# Connectors.net
KiCad netlist of a schematic drawn in Altium Designer
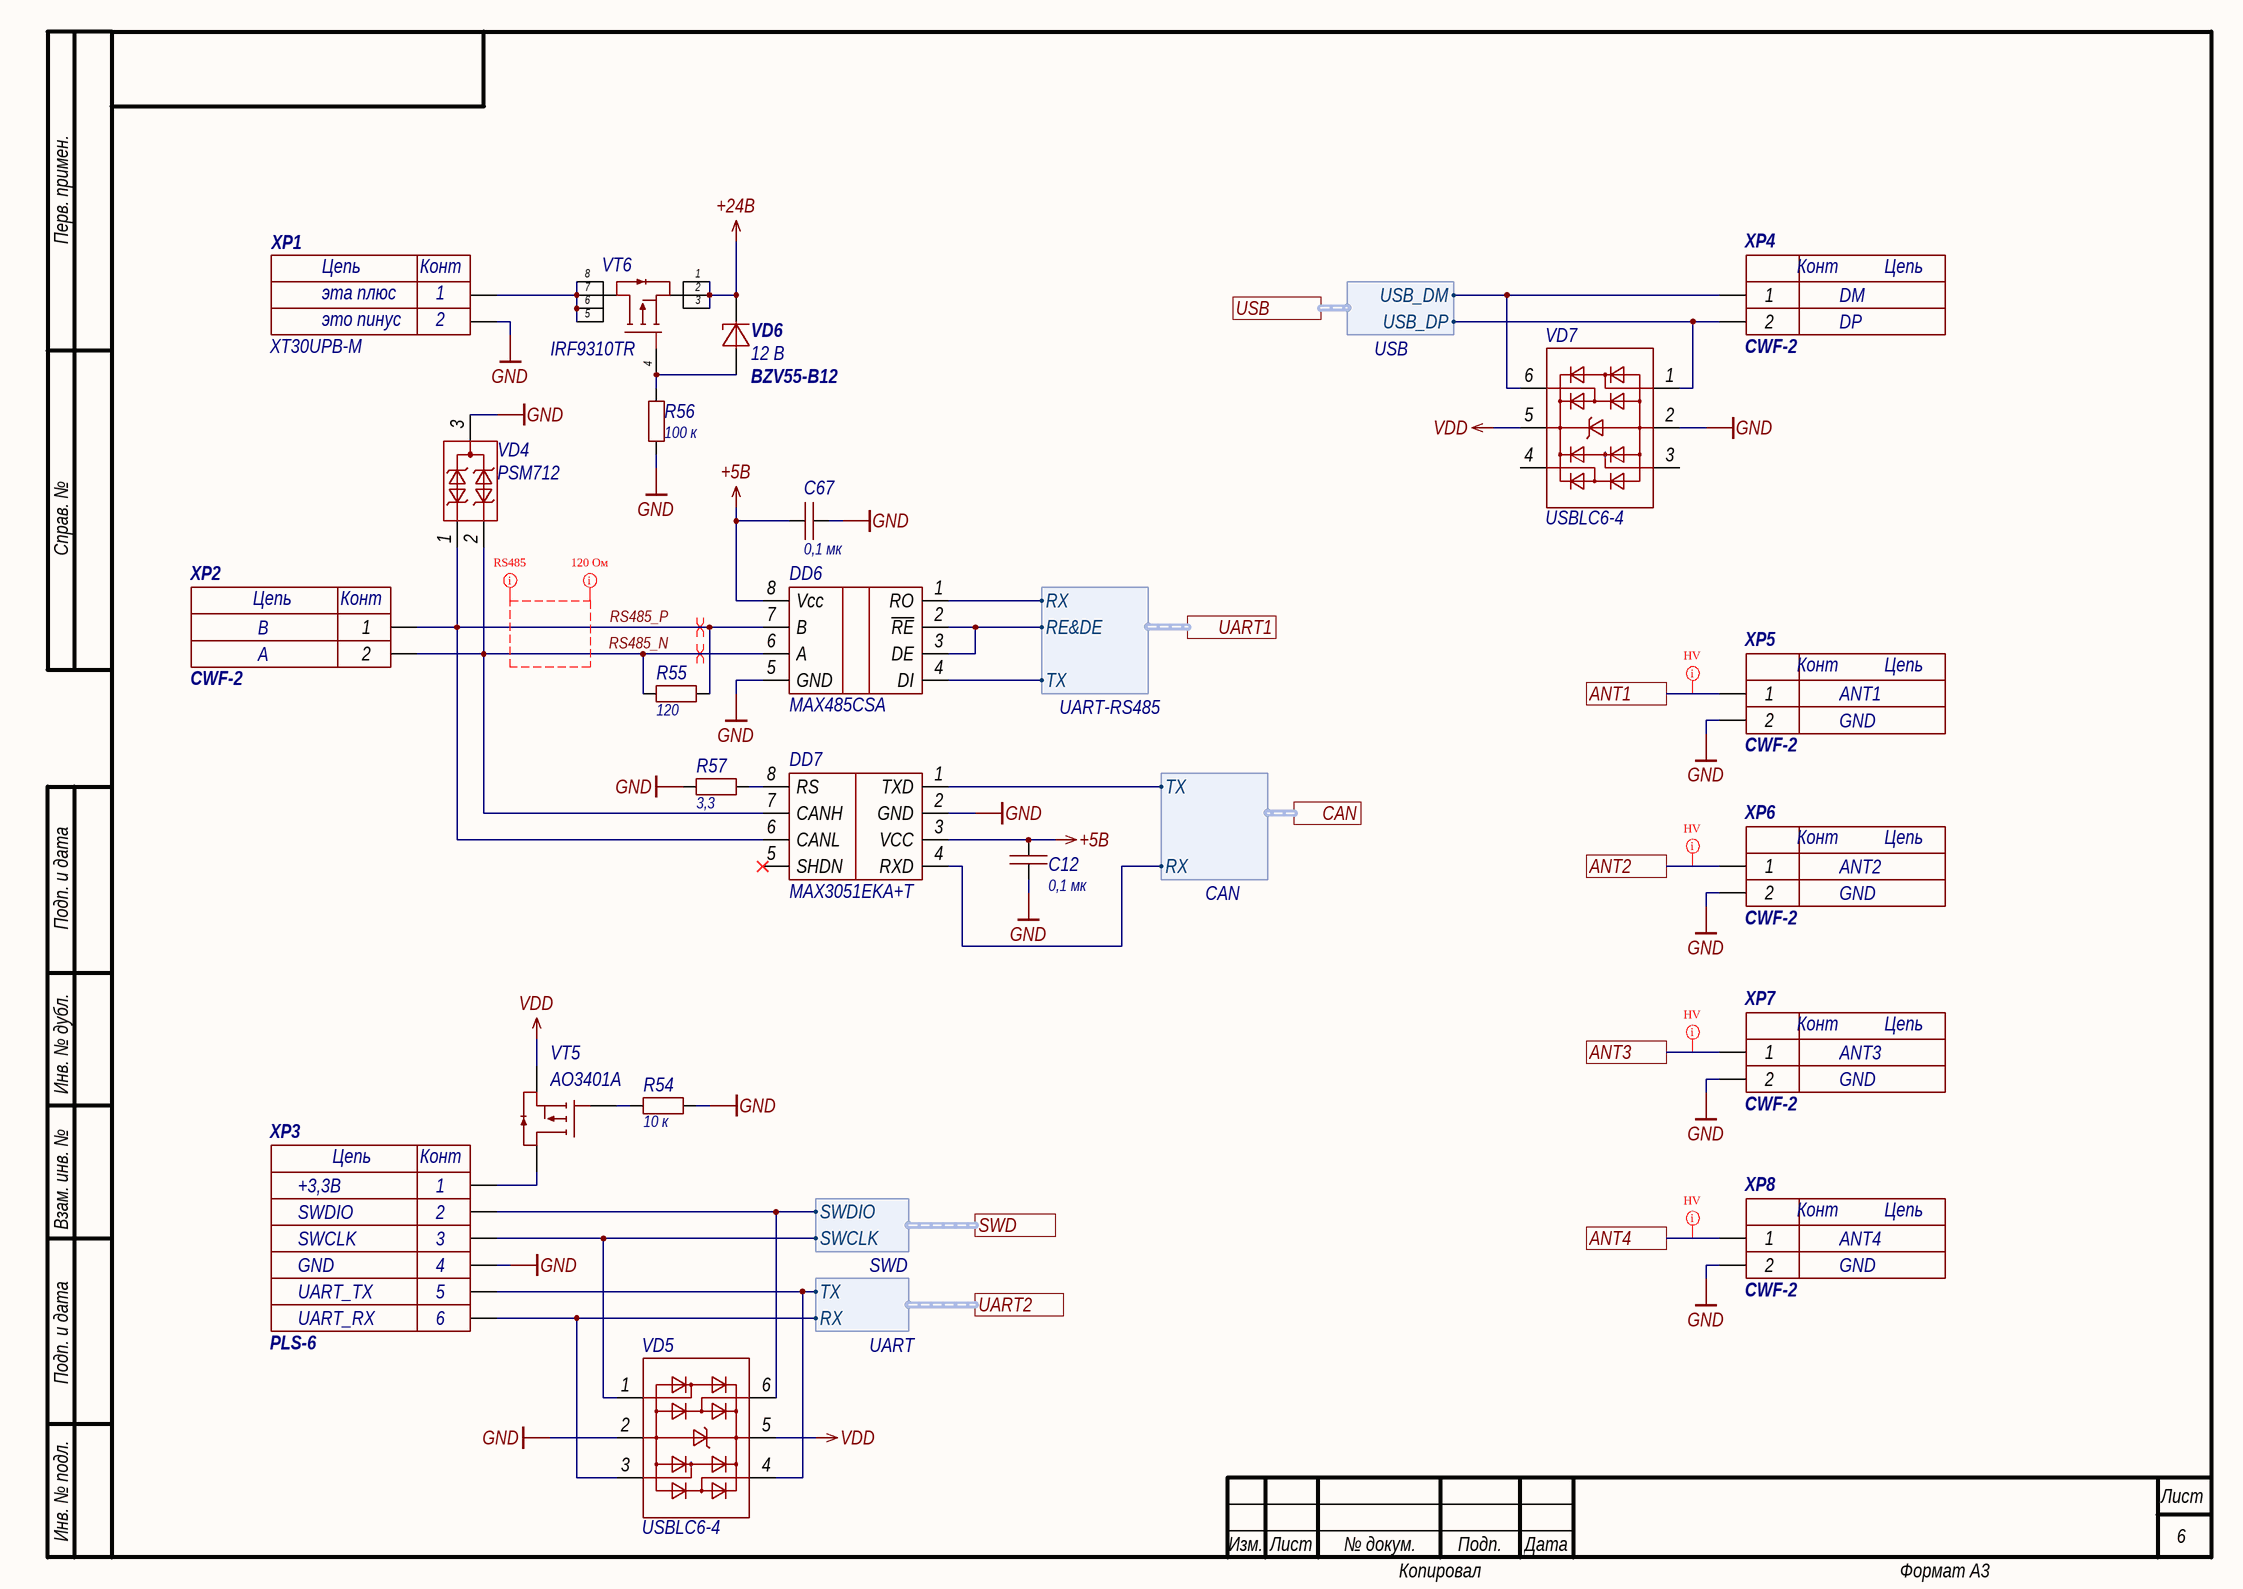
[diagram p0: Connectors.SchDoc]

(export (version "E")
  (design (tool "Eeschema 10.0.6"))
  (components
    (comp (ref "C12")
      (value "0,1 мк")
      (footprint "0603C")
      (description "Конденсатор 0603C ёмкостью 0,1 мк 10%, 50 В, X7R")
      (fields (field (name "PART NUMBER") "Capacitor_0,1u_10_50V_X7R_0603C") (field (name "TOLERANCE") "10%"))
      (libsource (lib "Hydrolib") (part "Capacitor"))
    )
    (comp (ref "C67")
      (value "0,1 мк")
      (footprint "0603C")
      (description "Конденсатор 0603C ёмкостью 0,1 мк 10%, 50 В, X7R")
      (fields (field (name "PART NUMBER") "Capacitor_0,1u_10_50V_X7R_0603C") (field (name "TOLERANCE") "10%"))
      (libsource (lib "Hydrolib") (part "Capacitor"))
    )
    (comp (ref "DD6")
      (value "MAX485CSA")
      (footprint "SOIC-8")
      (description "RS-485 приёмопередатчик")
      (libsource (lib "Hydrolib") (part "MAX485CSA"))
    )
    (comp (ref "DD7")
      (value "MAX3051EKA+T")
      (footprint "SOT23-8")
      (description "CAN трансивер 1Mbps +3.3В")
      (fields (field (name "АВТОР") "glebmih"))
      (libsource (lib "Hydrolib") (part "MAX3051EKA+T"))
    )
    (comp (ref "R54")
      (value "10 к")
      (footprint "0603R")
      (description "Резистор номиналом 10 кОм 1%")
      (fields (field (name "PART NUMBER") "Resistor_10k_1_0603") (field (name "TOLERANCE") "1%"))
      (libsource (lib "") (part "Resistor_1"))
    )
    (comp (ref "R55")
      (value "120")
      (footprint "1206R")
      (description "Резистор номиналом 120 Ом 1%")
      (fields
        (field (name "PART NUMBER") "Resistor_120_1_1206")
        (field (name "TOLERANCE") "1%")
        (field (name "АВТОР") "glebmih")
      )
      (libsource (lib "Hydrolib") (part "Resistor"))
    )
    (comp (ref "R56")
      (value "100 к")
      (footprint "0603R")
      (description "Резистор номиналом 100 кОм 1%")
      (fields (field (name "PART NUMBER") "Resistor_100k_1_0603") (field (name "TOLERANCE") "1%"))
      (libsource (lib "") (part "Resistor_2"))
    )
    (comp (ref "R57")
      (value "3,3")
      (footprint "0603R")
      (description "Резистор номиналом 3,3 Ом 1%")
      (fields (field (name "PART NUMBER") "Resistor_3.3_1_0603") (field (name "TOLERANCE") "1%"))
      (libsource (lib "Hydrolib") (part "Resistor"))
    )
    (comp (ref "VD4")
      (value "PSM712")
      (footprint "SOT23-3")
      (description "Защитный диод для линии RS-485")
      (libsource (lib "Hydrolib") (part "TVS_2_2dir"))
    )
    (comp (ref "VD5")
      (value "USBLC6-4")
      (footprint "SOT23-6")
      (description "Сборка защитных диодов для USB")
      (libsource (lib "Hydrolib") (part "USBLC6-4"))
    )
    (comp (ref "VD6")
      (value "BZV55-B12")
      (footprint "mini_MELF_3.5mm")
      (description "Стабилитрон 12В, 5%, 0.5Вт")
      (fields (field (name "ALTIUM_VALUE") "12 В") (field (name "АВТОР") "rreali"))
      (libsource (lib "Hydrolib") (part "Zener"))
    )
    (comp (ref "VD7")
      (value "USBLC6-4")
      (footprint "SOT23-6")
      (description "Сборка защитных диодов для USB")
      (libsource (lib "Hydrolib") (part "USBLC6-4"))
    )
    (comp (ref "VT5")
      (value "AO3401A")
      (footprint "SOT23-3")
      (description "P-канальный MOSFET")
      (libsource (lib "Hydrolib") (part "MOSFET P-channel 2"))
    )
    (comp (ref "VT6")
      (value "IRF9310TR")
      (footprint "SOIC-8")
      (description "P-канальный MOSFET, 30 В, 20 А")
      (fields (field (name "АВТОР") "glebmih"))
      (libsource (lib "Hydrolib") (part "MOSFET_P-channel_8pin"))
    )
    (comp (ref "XP1")
      (value "XT30UPB-M")
      (footprint "XT30UPB-M")
      (description "2-пиновый разъем с ключом")
      (fields
        (field (name "VALUE2") "это пинус")
        (field (name "VALUE1") "эта плюс")
        (field (name "АВТОР") "rreali")
      )
      (libsource (lib "Hydrolib") (part "Polar_Conn"))
    )
    (comp (ref "XP2")
      (value "CWF-2")
      (footprint "CWF-2")
      (description "2-пиновый разъем с ключом")
      (fields (field (name "АВТОР") "rreali"))
      (libsource (lib "Hydrolib") (part "Conn_2pin"))
    )
    (comp (ref "XP3")
      (value "PLS-6")
      (footprint "PLS6")
      (description "Гребенка 6 пинов")
      (fields (field (name "АВТОР") "glebmih"))
      (libsource (lib "Hydrolib") (part "Conn_6pin"))
    )
    (comp (ref "XP4")
      (value "CWF-2")
      (footprint "CWF-2")
      (description "2-пиновый разъем с ключом")
      (fields (field (name "АВТОР") "rreali"))
      (libsource (lib "Hydrolib") (part "Conn_2pin"))
    )
    (comp (ref "XP5")
      (value "CWF-2")
      (footprint "CWF-2")
      (description "2-пиновый разъем с ключом")
      (fields (field (name "АВТОР") "rreali"))
      (libsource (lib "Hydrolib") (part "Conn_2pin"))
    )
    (comp (ref "XP6")
      (value "CWF-2")
      (footprint "CWF-2")
      (description "2-пиновый разъем с ключом")
      (fields (field (name "АВТОР") "rreali"))
      (libsource (lib "Hydrolib") (part "Conn_2pin"))
    )
    (comp (ref "XP7")
      (value "CWF-2")
      (footprint "CWF-2")
      (description "2-пиновый разъем с ключом")
      (fields (field (name "АВТОР") "rreali"))
      (libsource (lib "Hydrolib") (part "Conn_2pin"))
    )
    (comp (ref "XP8")
      (value "CWF-2")
      (footprint "CWF-2")
      (description "2-пиновый разъем с ключом")
      (fields (field (name "АВТОР") "rreali"))
      (libsource (lib "Hydrolib") (part "Conn_2pin"))
    )
  )
  (nets
    (net (code "6") (name "+5В") (class "Default")
      (node (ref "C12") (pin "2") (pinfunction "2_2") (pintype "passive"))
      (node (ref "C67") (pin "1") (pinfunction "1_1") (pintype "passive"))
      (node (ref "DD6") (pin "8") (pinfunction "Vcc_8") (pintype "passive"))
      (node (ref "DD7") (pin "3") (pinfunction "VCC_3") (pintype "passive"))
    )
    (net (code "7") (name "+24В") (class "Default")
      (node (ref "VD6") (pin "2") (pinfunction "2_2") (pintype "passive"))
      (node (ref "VT6") (pin "1") (pinfunction "1_1") (pintype "passive"))
      (node (ref "VT6") (pin "2") (pinfunction "2_2") (pintype "passive"))
      (node (ref "VT6") (pin "3") (pinfunction "3_3") (pintype "passive"))
    )
    (net (code "8") (name "/ANT1") (class "Default")
      (node (ref "XP5") (pin "1") (pinfunction "1_1") (pintype "passive"))
    )
    (net (code "9") (name "/ANT2") (class "Default")
      (node (ref "XP6") (pin "1") (pinfunction "1_1") (pintype "passive"))
    )
    (net (code "10") (name "/ANT3") (class "Default")
      (node (ref "XP7") (pin "1") (pinfunction "1_1") (pintype "passive"))
    )
    (net (code "11") (name "/ANT4") (class "Default")
      (node (ref "XP8") (pin "1") (pinfunction "1_1") (pintype "passive"))
    )
    (net (code "12") (name "/RE&DE") (class "Default")
      (node (ref "DD6") (pin "2") (pinfunction "~{RE}_2") (pintype "passive"))
      (node (ref "DD6") (pin "3") (pinfunction "DE_3") (pintype "passive"))
    )
    (net (code "13") (name "/RS485_N") (class "Default")
      (node (ref "DD6") (pin "6") (pinfunction "A_6") (pintype "passive"))
      (node (ref "DD7") (pin "7") (pinfunction "CANH_7") (pintype "passive"))
      (node (ref "R55") (pin "1") (pinfunction "1_1") (pintype "passive"))
      (node (ref "VD4") (pin "2") (pinfunction "15_2") (pintype "passive"))
      (node (ref "XP2") (pin "2") (pinfunction "2_2") (pintype "passive"))
    )
    (net (code "14") (name "/RS485_P") (class "Default")
      (node (ref "DD6") (pin "7") (pinfunction "B_7") (pintype "passive"))
      (node (ref "DD7") (pin "6") (pinfunction "CANL_6") (pintype "passive"))
      (node (ref "R55") (pin "2") (pinfunction "2_2") (pintype "passive"))
      (node (ref "VD4") (pin "1") (pinfunction "14_1") (pintype "passive"))
      (node (ref "XP2") (pin "1") (pinfunction "1_1") (pintype "passive"))
    )
    (net (code "15") (name "/SWCLK") (class "Default")
      (node (ref "VD5") (pin "1") (pinfunction "9_1") (pintype "passive"))
      (node (ref "XP3") (pin "3") (pinfunction "3_3") (pintype "passive"))
    )
    (net (code "16") (name "/SWDIO") (class "Default")
      (node (ref "VD5") (pin "6") (pinfunction "14_6") (pintype "passive"))
      (node (ref "XP3") (pin "2") (pinfunction "2_2") (pintype "passive"))
    )
    (net (code "17") (name "/USB_DM") (class "Default")
      (node (ref "VD7") (pin "6") (pinfunction "14_6") (pintype "passive"))
      (node (ref "XP4") (pin "1") (pinfunction "1_1") (pintype "passive"))
    )
    (net (code "18") (name "/USB_DP") (class "Default")
      (node (ref "VD7") (pin "1") (pinfunction "9_1") (pintype "passive"))
      (node (ref "XP4") (pin "2") (pinfunction "2_2") (pintype "passive"))
    )
    (net (code "24") (name "GND") (class "Default")
      (node (ref "C12") (pin "1") (pinfunction "1_1") (pintype "passive"))
      (node (ref "C67") (pin "2") (pinfunction "2_2") (pintype "passive"))
      (node (ref "DD6") (pin "5") (pinfunction "GND_5") (pintype "passive"))
      (node (ref "DD7") (pin "2") (pinfunction "GND_2") (pintype "passive"))
      (node (ref "R54") (pin "1") (pinfunction "1_1") (pintype "passive"))
      (node (ref "R56") (pin "1") (pinfunction "1_1") (pintype "passive"))
      (node (ref "R57") (pin "1") (pinfunction "1_1") (pintype "passive"))
      (node (ref "VD4") (pin "3") (pinfunction "16_3") (pintype "passive"))
      (node (ref "VD5") (pin "2") (pinfunction "10_2") (pintype "passive"))
      (node (ref "VD7") (pin "2") (pinfunction "10_2") (pintype "passive"))
      (node (ref "XP1") (pin "N") (pinfunction "N_N") (pintype "passive"))
      (node (ref "XP3") (pin "4") (pinfunction "4_4") (pintype "passive"))
      (node (ref "XP5") (pin "2") (pinfunction "2_2") (pintype "passive"))
      (node (ref "XP6") (pin "2") (pinfunction "2_2") (pintype "passive"))
      (node (ref "XP7") (pin "2") (pinfunction "2_2") (pintype "passive"))
      (node (ref "XP8") (pin "2") (pinfunction "2_2") (pintype "passive"))
    )
    (net (code "25") (name "Net-(DD7-RS)") (class "Default")
      (node (ref "DD7") (pin "8") (pinfunction "RS_8") (pintype "passive"))
      (node (ref "R57") (pin "2") (pinfunction "2_2") (pintype "passive"))
    )
    (net (code "26") (name "Net-(R54-Pad2)") (class "Default")
      (node (ref "R54") (pin "2") (pinfunction "2_2") (pintype "passive"))
      (node (ref "VT5") (pin "1") (pinfunction "1_1") (pintype "passive"))
    )
    (net (code "27") (name "Net-(R56-Pad2)") (class "Default")
      (node (ref "R56") (pin "2") (pinfunction "2_2") (pintype "passive"))
      (node (ref "VD6") (pin "1") (pinfunction "1_1") (pintype "passive"))
      (node (ref "VT6") (pin "4") (pinfunction "4_4") (pintype "passive"))
    )
    (net (code "28") (name "Net-(VD5-11)") (class "Default")
      (node (ref "VD5") (pin "3") (pinfunction "11_3") (pintype "passive"))
      (node (ref "XP3") (pin "6") (pinfunction "6_6") (pintype "passive"))
    )
    (net (code "29") (name "Net-(VD5-12)") (class "Default")
      (node (ref "VD5") (pin "4") (pinfunction "12_4") (pintype "passive"))
      (node (ref "XP3") (pin "5") (pinfunction "5_5") (pintype "passive"))
    )
    (net (code "30") (name "Net-(VT5-Pad3)") (class "Default")
      (node (ref "VT5") (pin "3") (pinfunction "3_3") (pintype "passive"))
      (node (ref "XP3") (pin "1") (pinfunction "1_1") (pintype "passive"))
    )
    (net (code "31") (name "Net-(VT6-Pad5)") (class "Default")
      (node (ref "VT6") (pin "5") (pinfunction "5_5") (pintype "passive"))
      (node (ref "VT6") (pin "6") (pinfunction "6_6") (pintype "passive"))
      (node (ref "VT6") (pin "7") (pinfunction "7_7") (pintype "passive"))
      (node (ref "VT6") (pin "8") (pinfunction "8_8") (pintype "passive"))
      (node (ref "XP1") (pin "P") (pinfunction "P_P") (pintype "passive"))
    )
    (net (code "32") (name "VDD") (class "Default")
      (node (ref "VD5") (pin "5") (pinfunction "13_5") (pintype "passive"))
      (node (ref "VD7") (pin "5") (pinfunction "13_5") (pintype "passive"))
      (node (ref "VT5") (pin "2") (pinfunction "2_2") (pintype "passive"))
    )
    (net (code "33") (name "unconnected-(DD6-DI-Pad4)") (class "Default")
      (node (ref "DD6") (pin "4") (pinfunction "DI_4") (pintype "passive"))
    )
    (net (code "34") (name "unconnected-(DD6-RO-Pad1)") (class "Default")
      (node (ref "DD6") (pin "1") (pinfunction "RO_1") (pintype "passive"))
    )
    (net (code "35") (name "unconnected-(DD7-RXD-Pad4)") (class "Default")
      (node (ref "DD7") (pin "4") (pinfunction "RXD_4") (pintype "passive"))
    )
    (net (code "36") (name "unconnected-(DD7-SHDN-Pad5)") (class "Default")
      (node (ref "DD7") (pin "5") (pinfunction "SHDN_5") (pintype "passive+no_connect"))
    )
    (net (code "37") (name "unconnected-(DD7-TXD-Pad1)") (class "Default")
      (node (ref "DD7") (pin "1") (pinfunction "TXD_1") (pintype "passive"))
    )
    (net (code "38") (name "unconnected-(VD7-11-Pad3)") (class "Default")
      (node (ref "VD7") (pin "3") (pinfunction "11_3") (pintype "passive"))
    )
    (net (code "39") (name "unconnected-(VD7-12-Pad4)") (class "Default")
      (node (ref "VD7") (pin "4") (pinfunction "12_4") (pintype "passive"))
    )
  )
)
